# B167D.net
KiCad netlist of a schematic drawn in EAGLE
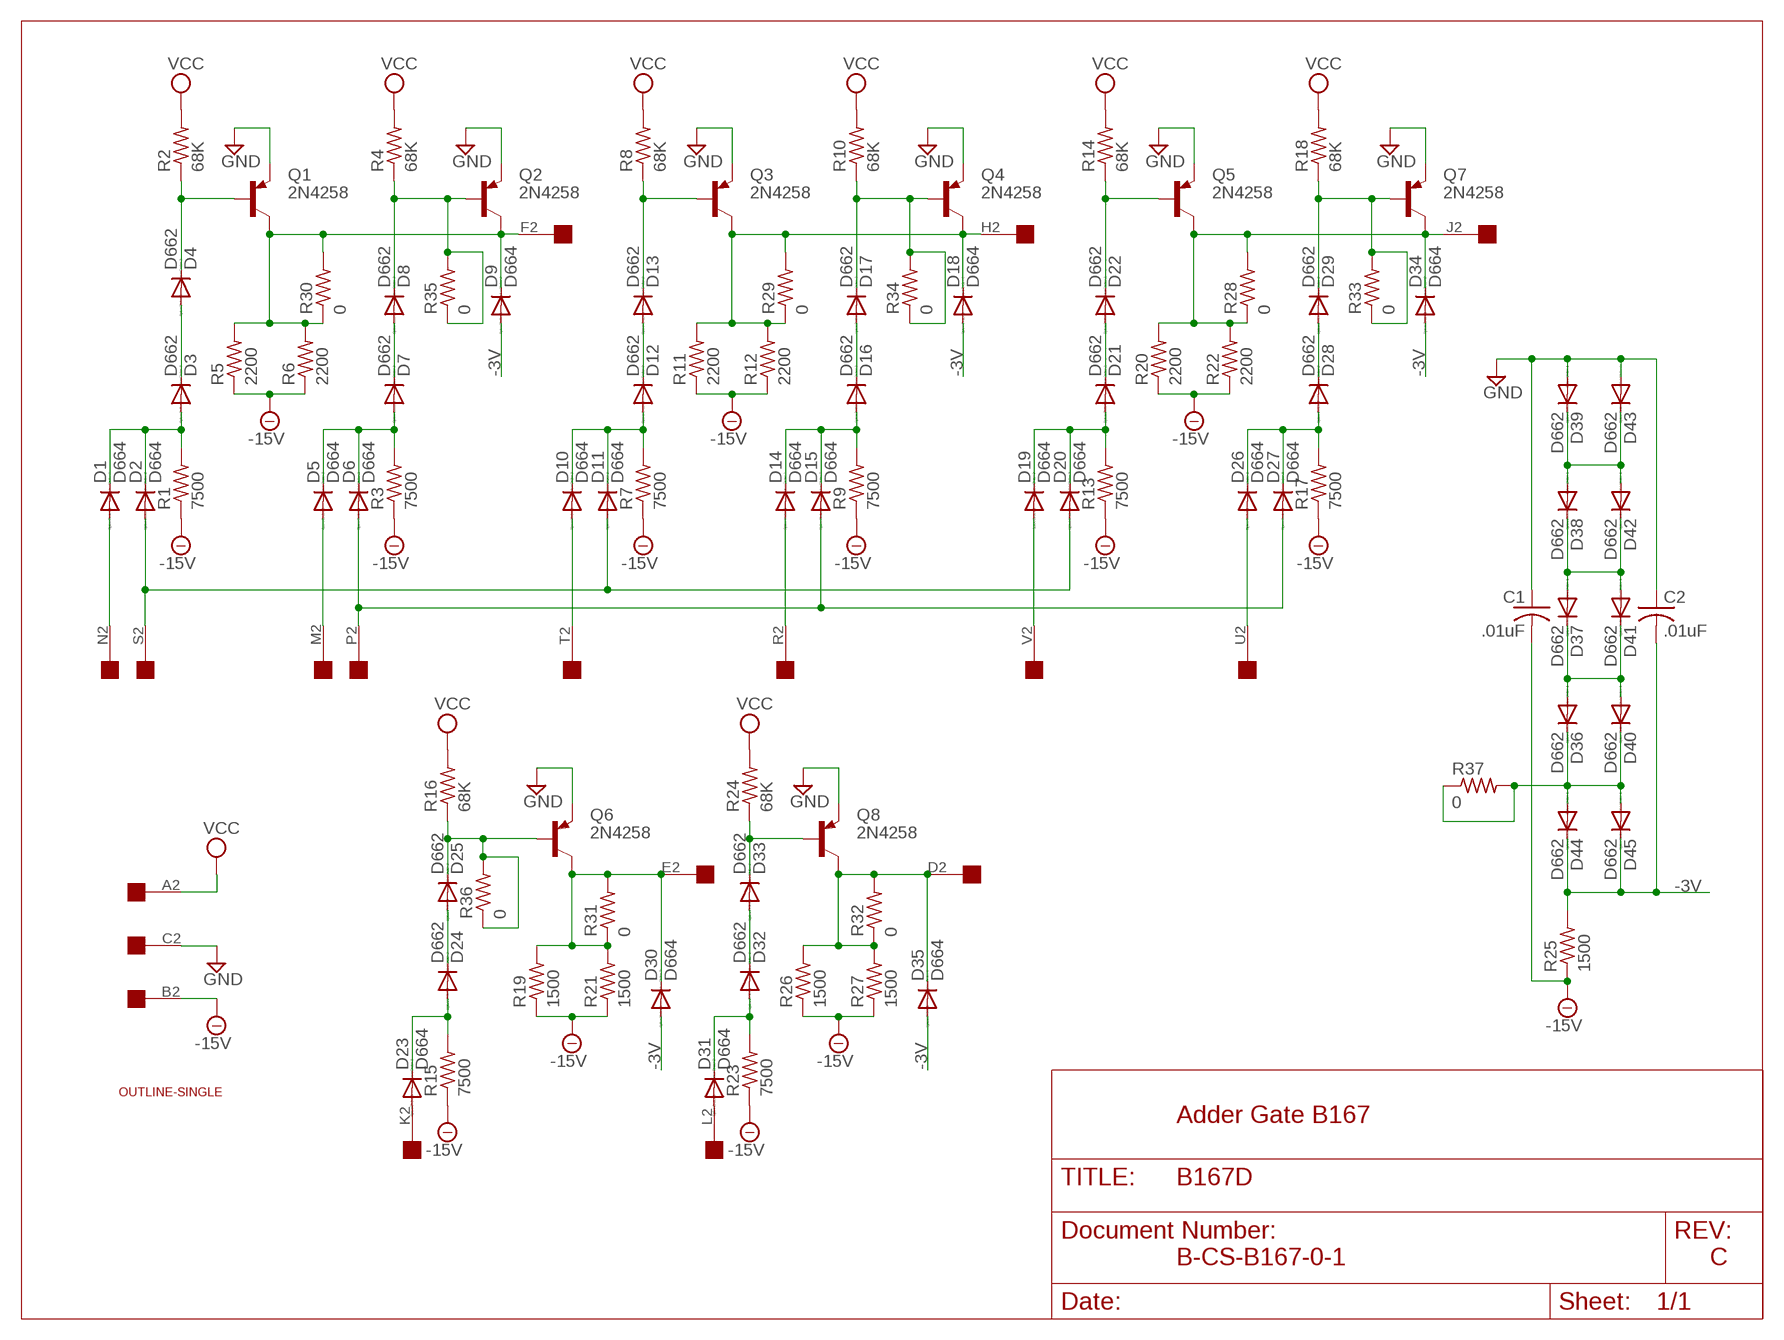
[diagram p0: schematic, sheet 1]

(export (version "E")
  (design (tool "Eeschema 10.0.6"))
  (components
    (comp (ref "C1")
      (value ".01uF")
      (footprint "eagle-import:C063-025X075")
      (libsource (lib "eagle-import") (part "C-US"))
    )
    (comp (ref "C2")
      (value ".01uF")
      (footprint "eagle-import:C063-025X075")
      (libsource (lib "eagle-import") (part "C-US"))
    )
    (comp (ref "D1")
      (value "D664")
      (footprint "eagle-import:DO35-10")
      (libsource (lib "eagle-import") (part "DIODE-DO35-10"))
    )
    (comp (ref "D2")
      (value "D664")
      (footprint "eagle-import:DO35-10")
      (libsource (lib "eagle-import") (part "DIODE-DO35-10"))
    )
    (comp (ref "D3")
      (value "D662")
      (footprint "eagle-import:DO35-10")
      (libsource (lib "eagle-import") (part "DIODE-DO35-10"))
    )
    (comp (ref "D4")
      (value "D662")
      (footprint "eagle-import:DO35-10")
      (libsource (lib "eagle-import") (part "DIODE-DO35-10"))
    )
    (comp (ref "D5")
      (value "D664")
      (footprint "eagle-import:DO35-10")
      (libsource (lib "eagle-import") (part "DIODE-DO35-10"))
    )
    (comp (ref "D6")
      (value "D664")
      (footprint "eagle-import:DO35-10")
      (libsource (lib "eagle-import") (part "DIODE-DO35-10"))
    )
    (comp (ref "D7")
      (value "D662")
      (footprint "eagle-import:DO35-10")
      (libsource (lib "eagle-import") (part "DIODE-DO35-10"))
    )
    (comp (ref "D8")
      (value "D662")
      (footprint "eagle-import:DO35-10")
      (libsource (lib "eagle-import") (part "DIODE-DO35-10"))
    )
    (comp (ref "D9")
      (value "D664")
      (footprint "eagle-import:DO35-10")
      (libsource (lib "eagle-import") (part "DIODE-DO35-10"))
    )
    (comp (ref "D10")
      (value "D664")
      (footprint "eagle-import:DO35-10")
      (libsource (lib "eagle-import") (part "DIODE-DO35-10"))
    )
    (comp (ref "D11")
      (value "D664")
      (footprint "eagle-import:DO35-10")
      (libsource (lib "eagle-import") (part "DIODE-DO35-10"))
    )
    (comp (ref "D12")
      (value "D662")
      (footprint "eagle-import:DO35-10")
      (libsource (lib "eagle-import") (part "DIODE-DO35-10"))
    )
    (comp (ref "D13")
      (value "D662")
      (footprint "eagle-import:DO35-10")
      (libsource (lib "eagle-import") (part "DIODE-DO35-10"))
    )
    (comp (ref "D14")
      (value "D664")
      (footprint "eagle-import:DO35-10")
      (libsource (lib "eagle-import") (part "DIODE-DO35-10"))
    )
    (comp (ref "D15")
      (value "D664")
      (footprint "eagle-import:DO35-10")
      (libsource (lib "eagle-import") (part "DIODE-DO35-10"))
    )
    (comp (ref "D16")
      (value "D662")
      (footprint "eagle-import:DO35-10")
      (libsource (lib "eagle-import") (part "DIODE-DO35-10"))
    )
    (comp (ref "D17")
      (value "D662")
      (footprint "eagle-import:DO35-10")
      (libsource (lib "eagle-import") (part "DIODE-DO35-10"))
    )
    (comp (ref "D18")
      (value "D664")
      (footprint "eagle-import:DO35-10")
      (libsource (lib "eagle-import") (part "DIODE-DO35-10"))
    )
    (comp (ref "D19")
      (value "D664")
      (footprint "eagle-import:DO35-10")
      (libsource (lib "eagle-import") (part "DIODE-DO35-10"))
    )
    (comp (ref "D20")
      (value "D664")
      (footprint "eagle-import:DO35-10")
      (libsource (lib "eagle-import") (part "DIODE-DO35-10"))
    )
    (comp (ref "D21")
      (value "D662")
      (footprint "eagle-import:DO35-10")
      (libsource (lib "eagle-import") (part "DIODE-DO35-10"))
    )
    (comp (ref "D22")
      (value "D662")
      (footprint "eagle-import:DO35-10")
      (libsource (lib "eagle-import") (part "DIODE-DO35-10"))
    )
    (comp (ref "D23")
      (value "D664")
      (footprint "eagle-import:DO35-10")
      (libsource (lib "eagle-import") (part "DIODE-DO35-10"))
    )
    (comp (ref "D24")
      (value "D662")
      (footprint "eagle-import:DO35-10")
      (libsource (lib "eagle-import") (part "DIODE-DO35-10"))
    )
    (comp (ref "D25")
      (value "D662")
      (footprint "eagle-import:DO35-10")
      (libsource (lib "eagle-import") (part "DIODE-DO35-10"))
    )
    (comp (ref "D26")
      (value "D664")
      (footprint "eagle-import:DO35-10")
      (libsource (lib "eagle-import") (part "DIODE-DO35-10"))
    )
    (comp (ref "D27")
      (value "D664")
      (footprint "eagle-import:DO35-10")
      (libsource (lib "eagle-import") (part "DIODE-DO35-10"))
    )
    (comp (ref "D28")
      (value "D662")
      (footprint "eagle-import:DO35-10")
      (libsource (lib "eagle-import") (part "DIODE-DO35-10"))
    )
    (comp (ref "D29")
      (value "D662")
      (footprint "eagle-import:DO35-10")
      (libsource (lib "eagle-import") (part "DIODE-DO35-10"))
    )
    (comp (ref "D30")
      (value "D664")
      (footprint "eagle-import:DO35-10")
      (libsource (lib "eagle-import") (part "DIODE-DO35-10"))
    )
    (comp (ref "D31")
      (value "D664")
      (footprint "eagle-import:DO35-10")
      (libsource (lib "eagle-import") (part "DIODE-DO35-10"))
    )
    (comp (ref "D32")
      (value "D662")
      (footprint "eagle-import:DO35-10")
      (libsource (lib "eagle-import") (part "DIODE-DO35-10"))
    )
    (comp (ref "D33")
      (value "D662")
      (footprint "eagle-import:DO35-10")
      (libsource (lib "eagle-import") (part "DIODE-DO35-10"))
    )
    (comp (ref "D34")
      (value "D664")
      (footprint "eagle-import:DO35-10")
      (libsource (lib "eagle-import") (part "DIODE-DO35-10"))
    )
    (comp (ref "D35")
      (value "D664")
      (footprint "eagle-import:DO35-10")
      (libsource (lib "eagle-import") (part "DIODE-DO35-10"))
    )
    (comp (ref "D36")
      (value "D662")
      (footprint "eagle-import:DO35-10")
      (libsource (lib "eagle-import") (part "DIODE-DO35-10"))
    )
    (comp (ref "D37")
      (value "D662")
      (footprint "eagle-import:DO35-10")
      (libsource (lib "eagle-import") (part "DIODE-DO35-10"))
    )
    (comp (ref "D38")
      (value "D662")
      (footprint "eagle-import:DO35-10")
      (libsource (lib "eagle-import") (part "DIODE-DO35-10"))
    )
    (comp (ref "D39")
      (value "D662")
      (footprint "eagle-import:DO35-10")
      (libsource (lib "eagle-import") (part "DIODE-DO35-10"))
    )
    (comp (ref "D40")
      (value "D662")
      (footprint "eagle-import:DO35-10")
      (libsource (lib "eagle-import") (part "DIODE-DO35-10"))
    )
    (comp (ref "D41")
      (value "D662")
      (footprint "eagle-import:DO35-10")
      (libsource (lib "eagle-import") (part "DIODE-DO35-10"))
    )
    (comp (ref "D42")
      (value "D662")
      (footprint "eagle-import:DO35-10")
      (libsource (lib "eagle-import") (part "DIODE-DO35-10"))
    )
    (comp (ref "D43")
      (value "D662")
      (footprint "eagle-import:DO35-10")
      (libsource (lib "eagle-import") (part "DIODE-DO35-10"))
    )
    (comp (ref "D44")
      (value "D662")
      (footprint "eagle-import:DO35-10")
      (libsource (lib "eagle-import") (part "DIODE-DO35-10"))
    )
    (comp (ref "D45")
      (value "D662")
      (footprint "eagle-import:DO35-10")
      (libsource (lib "eagle-import") (part "DIODE-DO35-10"))
    )
    (comp (ref "Q1")
      (value "2N4258")
      (footprint "eagle-import:TO5")
      (libsource (lib "eagle-import") (part "-PNP-TO5"))
    )
    (comp (ref "Q2")
      (value "2N4258")
      (footprint "eagle-import:TO5")
      (libsource (lib "eagle-import") (part "-PNP-TO5"))
    )
    (comp (ref "Q3")
      (value "2N4258")
      (footprint "eagle-import:TO5")
      (libsource (lib "eagle-import") (part "-PNP-TO5"))
    )
    (comp (ref "Q4")
      (value "2N4258")
      (footprint "eagle-import:TO5")
      (libsource (lib "eagle-import") (part "-PNP-TO5"))
    )
    (comp (ref "Q5")
      (value "2N4258")
      (footprint "eagle-import:TO5")
      (libsource (lib "eagle-import") (part "-PNP-TO5"))
    )
    (comp (ref "Q6")
      (value "2N4258")
      (footprint "eagle-import:TO5")
      (libsource (lib "eagle-import") (part "-PNP-TO5"))
    )
    (comp (ref "Q7")
      (value "2N4258")
      (footprint "eagle-import:TO5")
      (libsource (lib "eagle-import") (part "-PNP-TO5"))
    )
    (comp (ref "Q8")
      (value "2N4258")
      (footprint "eagle-import:TO5")
      (libsource (lib "eagle-import") (part "-PNP-TO5"))
    )
    (comp (ref "R1")
      (value "7500")
      (footprint "eagle-import:0207_10")
      (libsource (lib "eagle-import") (part "R-US_0207/10"))
    )
    (comp (ref "R2")
      (value "68K")
      (footprint "eagle-import:0207_10")
      (libsource (lib "eagle-import") (part "R-US_0207/10"))
    )
    (comp (ref "R3")
      (value "7500")
      (footprint "eagle-import:0207_10")
      (libsource (lib "eagle-import") (part "R-US_0207/10"))
    )
    (comp (ref "R4")
      (value "68K")
      (footprint "eagle-import:0207_10")
      (libsource (lib "eagle-import") (part "R-US_0207/10"))
    )
    (comp (ref "R5")
      (value "2200")
      (footprint "eagle-import:0207_10")
      (libsource (lib "eagle-import") (part "R-US_0207/10"))
    )
    (comp (ref "R6")
      (value "2200")
      (footprint "eagle-import:0207_10")
      (libsource (lib "eagle-import") (part "R-US_0207/10"))
    )
    (comp (ref "R7")
      (value "7500")
      (footprint "eagle-import:0207_10")
      (libsource (lib "eagle-import") (part "R-US_0207/10"))
    )
    (comp (ref "R8")
      (value "68K")
      (footprint "eagle-import:0207_10")
      (libsource (lib "eagle-import") (part "R-US_0207/10"))
    )
    (comp (ref "R9")
      (value "7500")
      (footprint "eagle-import:0207_10")
      (libsource (lib "eagle-import") (part "R-US_0207/10"))
    )
    (comp (ref "R10")
      (value "68K")
      (footprint "eagle-import:0207_10")
      (libsource (lib "eagle-import") (part "R-US_0207/10"))
    )
    (comp (ref "R11")
      (value "2200")
      (footprint "eagle-import:0207_10")
      (libsource (lib "eagle-import") (part "R-US_0207/10"))
    )
    (comp (ref "R12")
      (value "2200")
      (footprint "eagle-import:0207_10")
      (libsource (lib "eagle-import") (part "R-US_0207/10"))
    )
    (comp (ref "R13")
      (value "7500")
      (footprint "eagle-import:0207_10")
      (libsource (lib "eagle-import") (part "R-US_0207/10"))
    )
    (comp (ref "R14")
      (value "68K")
      (footprint "eagle-import:0207_10")
      (libsource (lib "eagle-import") (part "R-US_0207/10"))
    )
    (comp (ref "R15")
      (value "7500")
      (footprint "eagle-import:0207_10")
      (libsource (lib "eagle-import") (part "R-US_0207/10"))
    )
    (comp (ref "R16")
      (value "68K")
      (footprint "eagle-import:0207_10")
      (libsource (lib "eagle-import") (part "R-US_0207/10"))
    )
    (comp (ref "R17")
      (value "7500")
      (footprint "eagle-import:0207_10")
      (libsource (lib "eagle-import") (part "R-US_0207/10"))
    )
    (comp (ref "R18")
      (value "68K")
      (footprint "eagle-import:0207_10")
      (libsource (lib "eagle-import") (part "R-US_0207/10"))
    )
    (comp (ref "R19")
      (value "1500")
      (footprint "eagle-import:0207_10")
      (libsource (lib "eagle-import") (part "R-US_0207/10"))
    )
    (comp (ref "R20")
      (value "2200")
      (footprint "eagle-import:0207_10")
      (libsource (lib "eagle-import") (part "R-US_0207/10"))
    )
    (comp (ref "R21")
      (value "1500")
      (footprint "eagle-import:0207_10")
      (libsource (lib "eagle-import") (part "R-US_0207/10"))
    )
    (comp (ref "R22")
      (value "2200")
      (footprint "eagle-import:0207_10")
      (libsource (lib "eagle-import") (part "R-US_0207/10"))
    )
    (comp (ref "R23")
      (value "7500")
      (footprint "eagle-import:0207_10")
      (libsource (lib "eagle-import") (part "R-US_0207/10"))
    )
    (comp (ref "R24")
      (value "68K")
      (footprint "eagle-import:0207_10")
      (libsource (lib "eagle-import") (part "R-US_0207/10"))
    )
    (comp (ref "R25")
      (value "1500")
      (footprint "eagle-import:0207_10")
      (libsource (lib "eagle-import") (part "R-US_0207/10"))
    )
    (comp (ref "R26")
      (value "1500")
      (footprint "eagle-import:0207_10")
      (libsource (lib "eagle-import") (part "R-US_0207/10"))
    )
    (comp (ref "R27")
      (value "1500")
      (footprint "eagle-import:0207_10")
      (libsource (lib "eagle-import") (part "R-US_0207/10"))
    )
    (comp (ref "R28")
      (value "0")
      (footprint "eagle-import:0207_10")
      (libsource (lib "eagle-import") (part "R-US_0207/10"))
    )
    (comp (ref "R29")
      (value "0")
      (footprint "eagle-import:0207_10")
      (libsource (lib "eagle-import") (part "R-US_0207/10"))
    )
    (comp (ref "R30")
      (value "0")
      (footprint "eagle-import:0207_10")
      (libsource (lib "eagle-import") (part "R-US_0207/10"))
    )
    (comp (ref "R31")
      (value "0")
      (footprint "eagle-import:0207_10")
      (libsource (lib "eagle-import") (part "R-US_0207/10"))
    )
    (comp (ref "R32")
      (value "0")
      (footprint "eagle-import:0207_10")
      (libsource (lib "eagle-import") (part "R-US_0207/10"))
    )
    (comp (ref "R33")
      (value "0")
      (footprint "eagle-import:0207_10")
      (libsource (lib "eagle-import") (part "R-US_0207/10"))
    )
    (comp (ref "R34")
      (value "0")
      (footprint "eagle-import:0207_10")
      (libsource (lib "eagle-import") (part "R-US_0207/10"))
    )
    (comp (ref "R35")
      (value "0")
      (footprint "eagle-import:0207_10")
      (libsource (lib "eagle-import") (part "R-US_0207/10"))
    )
    (comp (ref "R36")
      (value "0")
      (footprint "eagle-import:0207_10")
      (libsource (lib "eagle-import") (part "R-US_0207/10"))
    )
    (comp (ref "R37")
      (value "0")
      (footprint "eagle-import:0207_10")
      (libsource (lib "eagle-import") (part "R-US_0207/10"))
    )
    (comp (ref "U$1")
      (value "OUTLINE-SINGLE")
      (footprint "eagle-import:SINGLE")
      (libsource (lib "eagle-import") (part "OUTLINE-SINGLE"))
    )
    (comp (ref "U$2")
      (value "EDGE-1")
      (footprint "eagle-import:EDGE-CON1")
      (libsource (lib "eagle-import") (part "EDGE-1"))
    )
  )
  (nets
    (net (code "1") (name "-15V") (class "Default")
      (node (ref "C1") (pin "2") (pinfunction "2_2") (pintype "passive"))
      (node (ref "R1") (pin "1") (pinfunction "1_1") (pintype "passive"))
      (node (ref "R11") (pin "1") (pinfunction "1_1") (pintype "passive"))
      (node (ref "R12") (pin "1") (pinfunction "1_1") (pintype "passive"))
      (node (ref "R13") (pin "1") (pinfunction "1_1") (pintype "passive"))
      (node (ref "R15") (pin "1") (pinfunction "1_1") (pintype "passive"))
      (node (ref "R17") (pin "1") (pinfunction "1_1") (pintype "passive"))
      (node (ref "R19") (pin "1") (pinfunction "1_1") (pintype "passive"))
      (node (ref "R20") (pin "1") (pinfunction "1_1") (pintype "passive"))
      (node (ref "R21") (pin "1") (pinfunction "1_1") (pintype "passive"))
      (node (ref "R22") (pin "1") (pinfunction "1_1") (pintype "passive"))
      (node (ref "R23") (pin "1") (pinfunction "1_1") (pintype "passive"))
      (node (ref "R25") (pin "1") (pinfunction "1_1") (pintype "passive"))
      (node (ref "R26") (pin "1") (pinfunction "1_1") (pintype "passive"))
      (node (ref "R27") (pin "1") (pinfunction "1_1") (pintype "passive"))
      (node (ref "R3") (pin "1") (pinfunction "1_1") (pintype "passive"))
      (node (ref "R5") (pin "1") (pinfunction "1_1") (pintype "passive"))
      (node (ref "R6") (pin "1") (pinfunction "1_1") (pintype "passive"))
      (node (ref "R7") (pin "1") (pinfunction "1_1") (pintype "passive"))
      (node (ref "R9") (pin "1") (pinfunction "1_1") (pintype "passive"))
      (node (ref "U$2") (pin "B2") (pinfunction "1_B2") (pintype "bidirectional"))
    )
    (net (code "2") (name "/-3V") (class "Default")
      (node (ref "C2") (pin "2") (pinfunction "2_2") (pintype "passive"))
      (node (ref "D18") (pin "A") (pinfunction "A_A") (pintype "passive"))
      (node (ref "D30") (pin "A") (pinfunction "A_A") (pintype "passive"))
      (node (ref "D34") (pin "A") (pinfunction "A_A") (pintype "passive"))
      (node (ref "D35") (pin "A") (pinfunction "A_A") (pintype "passive"))
      (node (ref "D44") (pin "C") (pinfunction "C_C") (pintype "passive"))
      (node (ref "D45") (pin "C") (pinfunction "C_C") (pintype "passive"))
      (node (ref "D9") (pin "A") (pinfunction "A_A") (pintype "passive"))
      (node (ref "R25") (pin "2") (pinfunction "2_2") (pintype "passive"))
    )
    (net (code "3") (name "GND") (class "Default")
      (node (ref "C1") (pin "1") (pinfunction "1_1") (pintype "passive"))
      (node (ref "C2") (pin "1") (pinfunction "1_1") (pintype "passive"))
      (node (ref "D39") (pin "A") (pinfunction "A_A") (pintype "passive"))
      (node (ref "D43") (pin "A") (pinfunction "A_A") (pintype "passive"))
      (node (ref "Q1") (pin "1") (pinfunction "E_1") (pintype "passive"))
      (node (ref "Q2") (pin "1") (pinfunction "E_1") (pintype "passive"))
      (node (ref "Q3") (pin "1") (pinfunction "E_1") (pintype "passive"))
      (node (ref "Q4") (pin "1") (pinfunction "E_1") (pintype "passive"))
      (node (ref "Q5") (pin "1") (pinfunction "E_1") (pintype "passive"))
      (node (ref "Q6") (pin "1") (pinfunction "E_1") (pintype "passive"))
      (node (ref "Q7") (pin "1") (pinfunction "E_1") (pintype "passive"))
      (node (ref "Q8") (pin "1") (pinfunction "E_1") (pintype "passive"))
      (node (ref "U$2") (pin "C2") (pinfunction "1_C2") (pintype "bidirectional"))
    )
    (net (code "4") (name "Net-(D1-PadC)") (class "Default")
      (node (ref "D1") (pin "C") (pinfunction "C_C") (pintype "passive"))
      (node (ref "D2") (pin "C") (pinfunction "C_C") (pintype "passive"))
      (node (ref "D3") (pin "A") (pinfunction "A_A") (pintype "passive"))
      (node (ref "R1") (pin "2") (pinfunction "2_2") (pintype "passive"))
    )
    (net (code "5") (name "Net-(D3-PadC)") (class "Default")
      (node (ref "D3") (pin "C") (pinfunction "C_C") (pintype "passive"))
      (node (ref "D4") (pin "A") (pinfunction "A_A") (pintype "passive"))
    )
    (net (code "6") (name "Net-(D5-PadC)") (class "Default")
      (node (ref "D5") (pin "C") (pinfunction "C_C") (pintype "passive"))
      (node (ref "D6") (pin "C") (pinfunction "C_C") (pintype "passive"))
      (node (ref "D7") (pin "A") (pinfunction "A_A") (pintype "passive"))
      (node (ref "R3") (pin "2") (pinfunction "2_2") (pintype "passive"))
    )
    (net (code "7") (name "Net-(D7-PadC)") (class "Default")
      (node (ref "D7") (pin "C") (pinfunction "C_C") (pintype "passive"))
      (node (ref "D8") (pin "A") (pinfunction "A_A") (pintype "passive"))
    )
    (net (code "8") (name "Net-(D10-PadC)") (class "Default")
      (node (ref "D10") (pin "C") (pinfunction "C_C") (pintype "passive"))
      (node (ref "D11") (pin "C") (pinfunction "C_C") (pintype "passive"))
      (node (ref "D12") (pin "A") (pinfunction "A_A") (pintype "passive"))
      (node (ref "R7") (pin "2") (pinfunction "2_2") (pintype "passive"))
    )
    (net (code "9") (name "Net-(D12-PadC)") (class "Default")
      (node (ref "D12") (pin "C") (pinfunction "C_C") (pintype "passive"))
      (node (ref "D13") (pin "A") (pinfunction "A_A") (pintype "passive"))
    )
    (net (code "10") (name "Net-(D14-PadC)") (class "Default")
      (node (ref "D14") (pin "C") (pinfunction "C_C") (pintype "passive"))
      (node (ref "D15") (pin "C") (pinfunction "C_C") (pintype "passive"))
      (node (ref "D16") (pin "A") (pinfunction "A_A") (pintype "passive"))
      (node (ref "R9") (pin "2") (pinfunction "2_2") (pintype "passive"))
    )
    (net (code "11") (name "Net-(D16-PadC)") (class "Default")
      (node (ref "D16") (pin "C") (pinfunction "C_C") (pintype "passive"))
      (node (ref "D17") (pin "A") (pinfunction "A_A") (pintype "passive"))
    )
    (net (code "12") (name "Net-(D19-PadC)") (class "Default")
      (node (ref "D19") (pin "C") (pinfunction "C_C") (pintype "passive"))
      (node (ref "D20") (pin "C") (pinfunction "C_C") (pintype "passive"))
      (node (ref "D21") (pin "A") (pinfunction "A_A") (pintype "passive"))
      (node (ref "R13") (pin "2") (pinfunction "2_2") (pintype "passive"))
    )
    (net (code "13") (name "Net-(D21-PadC)") (class "Default")
      (node (ref "D21") (pin "C") (pinfunction "C_C") (pintype "passive"))
      (node (ref "D22") (pin "A") (pinfunction "A_A") (pintype "passive"))
    )
    (net (code "14") (name "Net-(D23-PadC)") (class "Default")
      (node (ref "D23") (pin "C") (pinfunction "C_C") (pintype "passive"))
      (node (ref "D24") (pin "A") (pinfunction "A_A") (pintype "passive"))
      (node (ref "R15") (pin "2") (pinfunction "2_2") (pintype "passive"))
    )
    (net (code "15") (name "Net-(D24-PadC)") (class "Default")
      (node (ref "D24") (pin "C") (pinfunction "C_C") (pintype "passive"))
      (node (ref "D25") (pin "A") (pinfunction "A_A") (pintype "passive"))
    )
    (net (code "16") (name "Net-(D26-PadC)") (class "Default")
      (node (ref "D26") (pin "C") (pinfunction "C_C") (pintype "passive"))
      (node (ref "D27") (pin "C") (pinfunction "C_C") (pintype "passive"))
      (node (ref "D28") (pin "A") (pinfunction "A_A") (pintype "passive"))
      (node (ref "R17") (pin "2") (pinfunction "2_2") (pintype "passive"))
    )
    (net (code "17") (name "Net-(D28-PadC)") (class "Default")
      (node (ref "D28") (pin "C") (pinfunction "C_C") (pintype "passive"))
      (node (ref "D29") (pin "A") (pinfunction "A_A") (pintype "passive"))
    )
    (net (code "18") (name "Net-(D31-PadC)") (class "Default")
      (node (ref "D31") (pin "C") (pinfunction "C_C") (pintype "passive"))
      (node (ref "D32") (pin "A") (pinfunction "A_A") (pintype "passive"))
      (node (ref "R23") (pin "2") (pinfunction "2_2") (pintype "passive"))
    )
    (net (code "19") (name "Net-(D32-PadC)") (class "Default")
      (node (ref "D32") (pin "C") (pinfunction "C_C") (pintype "passive"))
      (node (ref "D33") (pin "A") (pinfunction "A_A") (pintype "passive"))
    )
    (net (code "20") (name "Net-(D36-PadA)") (class "Default")
      (node (ref "D36") (pin "A") (pinfunction "A_A") (pintype "passive"))
      (node (ref "D37") (pin "C") (pinfunction "C_C") (pintype "passive"))
      (node (ref "D40") (pin "A") (pinfunction "A_A") (pintype "passive"))
      (node (ref "D41") (pin "C") (pinfunction "C_C") (pintype "passive"))
    )
    (net (code "21") (name "Net-(D36-PadC)") (class "Default")
      (node (ref "D36") (pin "C") (pinfunction "C_C") (pintype "passive"))
      (node (ref "D40") (pin "C") (pinfunction "C_C") (pintype "passive"))
      (node (ref "D44") (pin "A") (pinfunction "A_A") (pintype "passive"))
      (node (ref "D45") (pin "A") (pinfunction "A_A") (pintype "passive"))
      (node (ref "R37") (pin "1") (pinfunction "1_1") (pintype "passive"))
      (node (ref "R37") (pin "2") (pinfunction "2_2") (pintype "passive"))
    )
    (net (code "22") (name "Net-(D37-PadA)") (class "Default")
      (node (ref "D37") (pin "A") (pinfunction "A_A") (pintype "passive"))
      (node (ref "D38") (pin "C") (pinfunction "C_C") (pintype "passive"))
      (node (ref "D41") (pin "A") (pinfunction "A_A") (pintype "passive"))
      (node (ref "D42") (pin "C") (pinfunction "C_C") (pintype "passive"))
    )
    (net (code "23") (name "Net-(D38-PadA)") (class "Default")
      (node (ref "D38") (pin "A") (pinfunction "A_A") (pintype "passive"))
      (node (ref "D39") (pin "C") (pinfunction "C_C") (pintype "passive"))
      (node (ref "D42") (pin "A") (pinfunction "A_A") (pintype "passive"))
      (node (ref "D43") (pin "C") (pinfunction "C_C") (pintype "passive"))
    )
    (net (code "24") (name "Net-(Q1-B)") (class "Default")
      (node (ref "D4") (pin "C") (pinfunction "C_C") (pintype "passive"))
      (node (ref "Q1") (pin "2") (pinfunction "B_2") (pintype "passive"))
      (node (ref "R2") (pin "1") (pinfunction "1_1") (pintype "passive"))
    )
    (net (code "25") (name "Net-(Q1-C)") (class "Default")
      (node (ref "D9") (pin "C") (pinfunction "C_C") (pintype "passive"))
      (node (ref "Q1") (pin "3") (pinfunction "C_3") (pintype "passive"))
      (node (ref "Q2") (pin "3") (pinfunction "C_3") (pintype "passive"))
      (node (ref "R30") (pin "1") (pinfunction "1_1") (pintype "passive"))
      (node (ref "R30") (pin "2") (pinfunction "2_2") (pintype "passive"))
      (node (ref "R5") (pin "2") (pinfunction "2_2") (pintype "passive"))
      (node (ref "R6") (pin "2") (pinfunction "2_2") (pintype "passive"))
      (node (ref "U$2") (pin "F2") (pinfunction "1_F2") (pintype "bidirectional"))
    )
    (net (code "26") (name "Net-(Q2-B)") (class "Default")
      (node (ref "D8") (pin "C") (pinfunction "C_C") (pintype "passive"))
      (node (ref "Q2") (pin "2") (pinfunction "B_2") (pintype "passive"))
      (node (ref "R35") (pin "1") (pinfunction "1_1") (pintype "passive"))
      (node (ref "R35") (pin "2") (pinfunction "2_2") (pintype "passive"))
      (node (ref "R4") (pin "1") (pinfunction "1_1") (pintype "passive"))
    )
    (net (code "27") (name "Net-(Q3-B)") (class "Default")
      (node (ref "D13") (pin "C") (pinfunction "C_C") (pintype "passive"))
      (node (ref "Q3") (pin "2") (pinfunction "B_2") (pintype "passive"))
      (node (ref "R8") (pin "1") (pinfunction "1_1") (pintype "passive"))
    )
    (net (code "28") (name "Net-(Q3-C)") (class "Default")
      (node (ref "D18") (pin "C") (pinfunction "C_C") (pintype "passive"))
      (node (ref "Q3") (pin "3") (pinfunction "C_3") (pintype "passive"))
      (node (ref "Q4") (pin "3") (pinfunction "C_3") (pintype "passive"))
      (node (ref "R11") (pin "2") (pinfunction "2_2") (pintype "passive"))
      (node (ref "R12") (pin "2") (pinfunction "2_2") (pintype "passive"))
      (node (ref "R29") (pin "1") (pinfunction "1_1") (pintype "passive"))
      (node (ref "R29") (pin "2") (pinfunction "2_2") (pintype "passive"))
      (node (ref "U$2") (pin "H2") (pinfunction "1_H2") (pintype "bidirectional"))
    )
    (net (code "29") (name "Net-(Q4-B)") (class "Default")
      (node (ref "D17") (pin "C") (pinfunction "C_C") (pintype "passive"))
      (node (ref "Q4") (pin "2") (pinfunction "B_2") (pintype "passive"))
      (node (ref "R10") (pin "1") (pinfunction "1_1") (pintype "passive"))
      (node (ref "R34") (pin "1") (pinfunction "1_1") (pintype "passive"))
      (node (ref "R34") (pin "2") (pinfunction "2_2") (pintype "passive"))
    )
    (net (code "30") (name "Net-(Q5-B)") (class "Default")
      (node (ref "D22") (pin "C") (pinfunction "C_C") (pintype "passive"))
      (node (ref "Q5") (pin "2") (pinfunction "B_2") (pintype "passive"))
      (node (ref "R14") (pin "1") (pinfunction "1_1") (pintype "passive"))
    )
    (net (code "31") (name "Net-(Q5-C)") (class "Default")
      (node (ref "D34") (pin "C") (pinfunction "C_C") (pintype "passive"))
      (node (ref "Q5") (pin "3") (pinfunction "C_3") (pintype "passive"))
      (node (ref "Q7") (pin "3") (pinfunction "C_3") (pintype "passive"))
      (node (ref "R20") (pin "2") (pinfunction "2_2") (pintype "passive"))
      (node (ref "R22") (pin "2") (pinfunction "2_2") (pintype "passive"))
      (node (ref "R28") (pin "1") (pinfunction "1_1") (pintype "passive"))
      (node (ref "R28") (pin "2") (pinfunction "2_2") (pintype "passive"))
      (node (ref "U$2") (pin "J2") (pinfunction "1_J2") (pintype "bidirectional"))
    )
    (net (code "32") (name "Net-(Q6-B)") (class "Default")
      (node (ref "D25") (pin "C") (pinfunction "C_C") (pintype "passive"))
      (node (ref "Q6") (pin "2") (pinfunction "B_2") (pintype "passive"))
      (node (ref "R16") (pin "1") (pinfunction "1_1") (pintype "passive"))
      (node (ref "R36") (pin "1") (pinfunction "1_1") (pintype "passive"))
      (node (ref "R36") (pin "2") (pinfunction "2_2") (pintype "passive"))
    )
    (net (code "33") (name "Net-(Q6-C)") (class "Default")
      (node (ref "D30") (pin "C") (pinfunction "C_C") (pintype "passive"))
      (node (ref "Q6") (pin "3") (pinfunction "C_3") (pintype "passive"))
      (node (ref "R19") (pin "2") (pinfunction "2_2") (pintype "passive"))
      (node (ref "R21") (pin "2") (pinfunction "2_2") (pintype "passive"))
      (node (ref "R31") (pin "1") (pinfunction "1_1") (pintype "passive"))
      (node (ref "R31") (pin "2") (pinfunction "2_2") (pintype "passive"))
      (node (ref "U$2") (pin "E2") (pinfunction "1_E2") (pintype "bidirectional"))
    )
    (net (code "34") (name "Net-(Q7-B)") (class "Default")
      (node (ref "D29") (pin "C") (pinfunction "C_C") (pintype "passive"))
      (node (ref "Q7") (pin "2") (pinfunction "B_2") (pintype "passive"))
      (node (ref "R18") (pin "1") (pinfunction "1_1") (pintype "passive"))
      (node (ref "R33") (pin "1") (pinfunction "1_1") (pintype "passive"))
      (node (ref "R33") (pin "2") (pinfunction "2_2") (pintype "passive"))
    )
    (net (code "35") (name "Net-(Q8-B)") (class "Default")
      (node (ref "D33") (pin "C") (pinfunction "C_C") (pintype "passive"))
      (node (ref "Q8") (pin "2") (pinfunction "B_2") (pintype "passive"))
      (node (ref "R24") (pin "1") (pinfunction "1_1") (pintype "passive"))
    )
    (net (code "36") (name "Net-(Q8-C)") (class "Default")
      (node (ref "D35") (pin "C") (pinfunction "C_C") (pintype "passive"))
      (node (ref "Q8") (pin "3") (pinfunction "C_3") (pintype "passive"))
      (node (ref "R26") (pin "2") (pinfunction "2_2") (pintype "passive"))
      (node (ref "R27") (pin "2") (pinfunction "2_2") (pintype "passive"))
      (node (ref "R32") (pin "1") (pinfunction "1_1") (pintype "passive"))
      (node (ref "R32") (pin "2") (pinfunction "2_2") (pintype "passive"))
      (node (ref "U$2") (pin "D2") (pinfunction "1_D2") (pintype "bidirectional"))
    )
    (net (code "37") (name "Net-(U$2I-1)") (class "Default")
      (node (ref "D23") (pin "A") (pinfunction "A_A") (pintype "passive"))
      (node (ref "U$2") (pin "K2") (pinfunction "1_K2") (pintype "bidirectional"))
    )
    (net (code "38") (name "Net-(U$2J-1)") (class "Default")
      (node (ref "D31") (pin "A") (pinfunction "A_A") (pintype "passive"))
      (node (ref "U$2") (pin "L2") (pinfunction "1_L2") (pintype "bidirectional"))
    )
    (net (code "39") (name "Net-(U$2K-1)") (class "Default")
      (node (ref "D5") (pin "A") (pinfunction "A_A") (pintype "passive"))
      (node (ref "U$2") (pin "M2") (pinfunction "1_M2") (pintype "bidirectional"))
    )
    (net (code "40") (name "Net-(U$2L-1)") (class "Default")
      (node (ref "D1") (pin "A") (pinfunction "A_A") (pintype "passive"))
      (node (ref "U$2") (pin "N2") (pinfunction "1_N2") (pintype "bidirectional"))
    )
    (net (code "41") (name "Net-(U$2M-1)") (class "Default")
      (node (ref "D15") (pin "A") (pinfunction "A_A") (pintype "passive"))
      (node (ref "D27") (pin "A") (pinfunction "A_A") (pintype "passive"))
      (node (ref "D6") (pin "A") (pinfunction "A_A") (pintype "passive"))
      (node (ref "U$2") (pin "P2") (pinfunction "1_P2") (pintype "bidirectional"))
    )
    (net (code "42") (name "Net-(U$2N-1)") (class "Default")
      (node (ref "D14") (pin "A") (pinfunction "A_A") (pintype "passive"))
      (node (ref "U$2") (pin "R2") (pinfunction "1_R2") (pintype "bidirectional"))
    )
    (net (code "43") (name "Net-(U$2O-1)") (class "Default")
      (node (ref "D11") (pin "A") (pinfunction "A_A") (pintype "passive"))
      (node (ref "D2") (pin "A") (pinfunction "A_A") (pintype "passive"))
      (node (ref "D20") (pin "A") (pinfunction "A_A") (pintype "passive"))
      (node (ref "U$2") (pin "S2") (pinfunction "1_S2") (pintype "bidirectional"))
    )
    (net (code "44") (name "Net-(U$2P-1)") (class "Default")
      (node (ref "D10") (pin "A") (pinfunction "A_A") (pintype "passive"))
      (node (ref "U$2") (pin "T2") (pinfunction "1_T2") (pintype "bidirectional"))
    )
    (net (code "45") (name "Net-(U$2Q-1)") (class "Default")
      (node (ref "D26") (pin "A") (pinfunction "A_A") (pintype "passive"))
      (node (ref "U$2") (pin "U2") (pinfunction "1_U2") (pintype "bidirectional"))
    )
    (net (code "46") (name "Net-(U$2R-1)") (class "Default")
      (node (ref "D19") (pin "A") (pinfunction "A_A") (pintype "passive"))
      (node (ref "U$2") (pin "V2") (pinfunction "1_V2") (pintype "bidirectional"))
    )
    (net (code "47") (name "VCC") (class "Default")
      (node (ref "R10") (pin "2") (pinfunction "2_2") (pintype "passive"))
      (node (ref "R14") (pin "2") (pinfunction "2_2") (pintype "passive"))
      (node (ref "R16") (pin "2") (pinfunction "2_2") (pintype "passive"))
      (node (ref "R18") (pin "2") (pinfunction "2_2") (pintype "passive"))
      (node (ref "R2") (pin "2") (pinfunction "2_2") (pintype "passive"))
      (node (ref "R24") (pin "2") (pinfunction "2_2") (pintype "passive"))
      (node (ref "R4") (pin "2") (pinfunction "2_2") (pintype "passive"))
      (node (ref "R8") (pin "2") (pinfunction "2_2") (pintype "passive"))
      (node (ref "U$2") (pin "A2") (pinfunction "1_A2") (pintype "bidirectional"))
    )
  )
)
